# HF_front.net
KiCad netlist of a schematic drawn in EAGLE
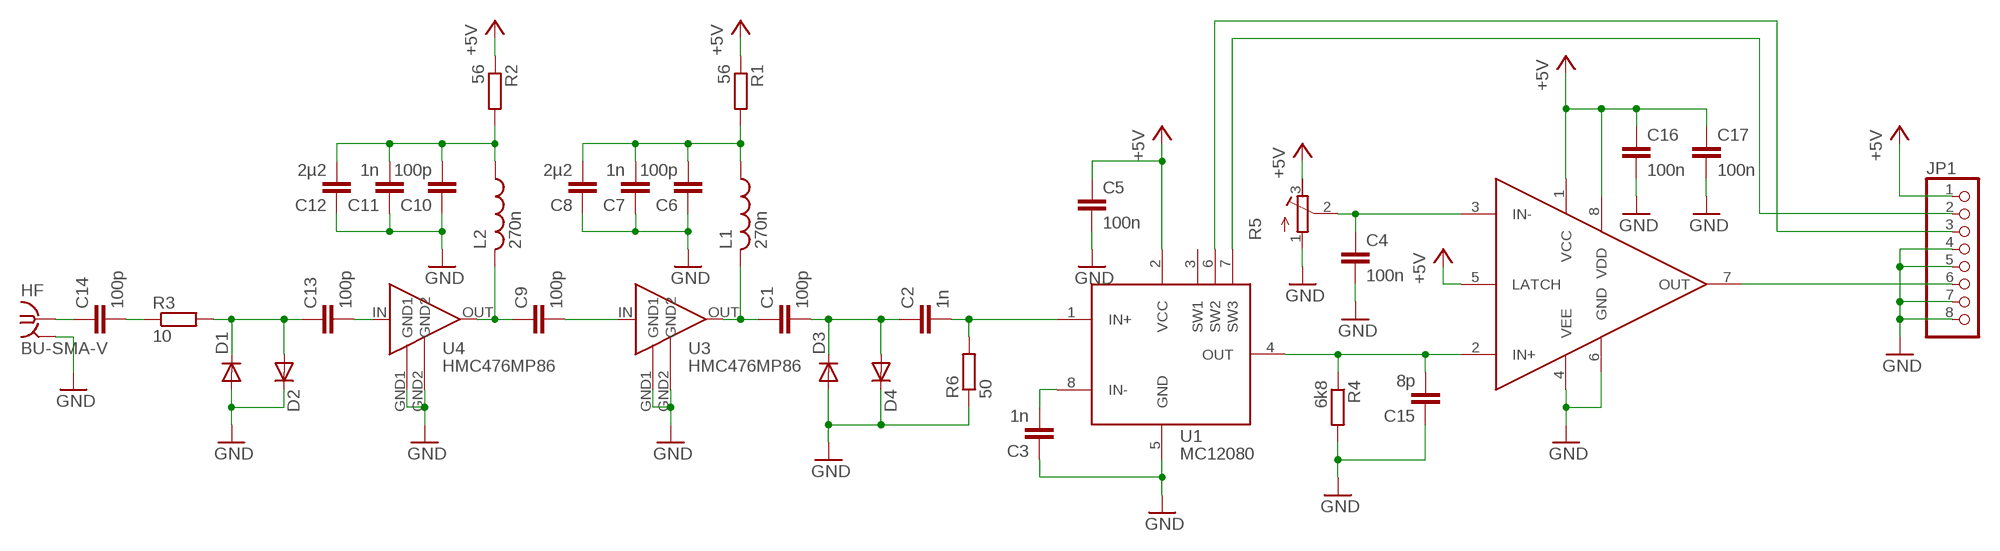
[diagram p0: schematic, sheet 1]

(export (version "E")
  (design (tool "Eeschema 10.0.6"))
  (components
    (comp (ref "C1")
      (value "100p")
      (footprint "eagle-import:C0603")
      (libsource (lib "eagle-import") (part "C-EUC0603"))
    )
    (comp (ref "C2")
      (value "1n")
      (footprint "eagle-import:C0603")
      (libsource (lib "eagle-import") (part "C-EUC0603"))
    )
    (comp (ref "C3")
      (value "1n")
      (footprint "eagle-import:C0603")
      (libsource (lib "eagle-import") (part "C-EUC0603"))
    )
    (comp (ref "C4")
      (value "100n")
      (footprint "eagle-import:C0603")
      (libsource (lib "eagle-import") (part "C-EUC0603"))
    )
    (comp (ref "C5")
      (value "100n")
      (footprint "eagle-import:C0603")
      (libsource (lib "eagle-import") (part "C-EUC0603"))
    )
    (comp (ref "C6")
      (value "100p")
      (footprint "eagle-import:C0603")
      (libsource (lib "eagle-import") (part "C-EUC0603"))
    )
    (comp (ref "C7")
      (value "1n")
      (footprint "eagle-import:C0603")
      (libsource (lib "eagle-import") (part "C-EUC0603"))
    )
    (comp (ref "C8")
      (value "2µ2")
      (footprint "eagle-import:C0603")
      (libsource (lib "eagle-import") (part "C-EUC0603"))
    )
    (comp (ref "C9")
      (value "100p")
      (footprint "eagle-import:C0603")
      (libsource (lib "eagle-import") (part "C-EUC0603"))
    )
    (comp (ref "C10")
      (value "100p")
      (footprint "eagle-import:C0603")
      (libsource (lib "eagle-import") (part "C-EUC0603"))
    )
    (comp (ref "C11")
      (value "1n")
      (footprint "eagle-import:C0603")
      (libsource (lib "eagle-import") (part "C-EUC0603"))
    )
    (comp (ref "C12")
      (value "2µ2")
      (footprint "eagle-import:C0603")
      (libsource (lib "eagle-import") (part "C-EUC0603"))
    )
    (comp (ref "C13")
      (value "100p")
      (footprint "eagle-import:C0603")
      (libsource (lib "eagle-import") (part "C-EUC0603"))
    )
    (comp (ref "C14")
      (value "100p")
      (footprint "eagle-import:C0603")
      (libsource (lib "eagle-import") (part "C-EUC0603"))
    )
    (comp (ref "C15")
      (value "8p")
      (footprint "eagle-import:C0603")
      (libsource (lib "eagle-import") (part "C-EUC0603"))
    )
    (comp (ref "C16")
      (value "100n")
      (footprint "eagle-import:C0603")
      (libsource (lib "eagle-import") (part "C-EUC0603"))
    )
    (comp (ref "C17")
      (value "100n")
      (footprint "eagle-import:C0603")
      (libsource (lib "eagle-import") (part "C-EUC0603"))
    )
    (comp (ref "D1")
      (value "DIODE-SOD323-W")
      (footprint "eagle-import:SOD323-W")
      (libsource (lib "eagle-import") (part "DIODE-SOD323-W"))
    )
    (comp (ref "D2")
      (value "DIODE-SOD323-W")
      (footprint "eagle-import:SOD323-W")
      (libsource (lib "eagle-import") (part "DIODE-SOD323-W"))
    )
    (comp (ref "D3")
      (value "DIODE-SOD323-W")
      (footprint "eagle-import:SOD323-W")
      (libsource (lib "eagle-import") (part "DIODE-SOD323-W"))
    )
    (comp (ref "D4")
      (value "DIODE-SOD323-W")
      (footprint "eagle-import:SOD323-W")
      (libsource (lib "eagle-import") (part "DIODE-SOD323-W"))
    )
    (comp (ref "HF")
      (value "BU-SMA-V")
      (footprint "eagle-import:BU-SMA-V")
      (libsource (lib "eagle-import") (part "BU-SMA-V"))
    )
    (comp (ref "JP1")
      (value "PINHD-1X8")
      (footprint "eagle-import:1X08")
      (libsource (lib "eagle-import") (part "PINHD-1X8"))
    )
    (comp (ref "L1")
      (value "270n")
      (footprint "eagle-import:R0603")
      (libsource (lib "eagle-import") (part "INDUCTOR0603"))
    )
    (comp (ref "L2")
      (value "270n")
      (footprint "eagle-import:R0603")
      (libsource (lib "eagle-import") (part "INDUCTOR0603"))
    )
    (comp (ref "R1")
      (value "56")
      (footprint "eagle-import:R0603")
      (libsource (lib "eagle-import") (part "R-EU_R0603"))
    )
    (comp (ref "R2")
      (value "56")
      (footprint "eagle-import:R0603")
      (libsource (lib "eagle-import") (part "R-EU_R0603"))
    )
    (comp (ref "R3")
      (value "10")
      (footprint "eagle-import:R0603")
      (libsource (lib "eagle-import") (part "R-EU_R0603"))
    )
    (comp (ref "R4")
      (value "6k8")
      (footprint "eagle-import:R0603")
      (libsource (lib "eagle-import") (part "R-EU_R0603"))
    )
    (comp (ref "R5")
      (value "R-TRIMM64W")
      (footprint "eagle-import:RTRIM64W")
      (libsource (lib "eagle-import") (part "R-TRIMM64W"))
    )
    (comp (ref "R6")
      (value "50")
      (footprint "eagle-import:R0603")
      (libsource (lib "eagle-import") (part "R-EU_R0603"))
    )
    (comp (ref "U1")
      (value "MC12080")
      (footprint "eagle-import:SOIC8")
      (libsource (lib "eagle-import") (part "MC12080"))
    )
    (comp (ref "U2")
      (value "MAX9203")
      (footprint "eagle-import:SOIC8")
      (libsource (lib "eagle-import") (part "MAX9203"))
    )
    (comp (ref "U3")
      (value "HMC476MP86")
      (footprint "eagle-import:MICRO-X")
      (libsource (lib "eagle-import") (part "HMC476MP86"))
    )
    (comp (ref "U4")
      (value "HMC476MP86")
      (footprint "eagle-import:MICRO-X")
      (libsource (lib "eagle-import") (part "HMC476MP86"))
    )
  )
  (nets
    (net (code "1") (name "+5V") (class "Default")
      (node (ref "C16") (pin "1") (pinfunction "1_1") (pintype "passive"))
      (node (ref "C17") (pin "1") (pinfunction "1_1") (pintype "passive"))
      (node (ref "C5") (pin "1") (pinfunction "1_1") (pintype "passive"))
      (node (ref "JP1") (pin "1") (pinfunction "1_1") (pintype "passive"))
      (node (ref "R1") (pin "1") (pinfunction "1_1") (pintype "passive"))
      (node (ref "R2") (pin "1") (pinfunction "1_1") (pintype "passive"))
      (node (ref "R5") (pin "3") (pinfunction "A_3") (pintype "passive"))
      (node (ref "U1") (pin "2") (pinfunction "VCC_2") (pintype "bidirectional"))
      (node (ref "U2") (pin "1") (pinfunction "VCC_1") (pintype "bidirectional"))
      (node (ref "U2") (pin "5") (pinfunction "LATCH_5") (pintype "bidirectional"))
      (node (ref "U2") (pin "8") (pinfunction "VDD_8") (pintype "bidirectional"))
    )
    (net (code "2") (name "GND") (class "Default")
      (node (ref "C10") (pin "1") (pinfunction "1_1") (pintype "passive"))
      (node (ref "C11") (pin "1") (pinfunction "1_1") (pintype "passive"))
      (node (ref "C12") (pin "1") (pinfunction "1_1") (pintype "passive"))
      (node (ref "C15") (pin "1") (pinfunction "1_1") (pintype "passive"))
      (node (ref "C16") (pin "2") (pinfunction "2_2") (pintype "passive"))
      (node (ref "C17") (pin "2") (pinfunction "2_2") (pintype "passive"))
      (node (ref "C3") (pin "1") (pinfunction "1_1") (pintype "passive"))
      (node (ref "C4") (pin "2") (pinfunction "2_2") (pintype "passive"))
      (node (ref "C5") (pin "2") (pinfunction "2_2") (pintype "passive"))
      (node (ref "C6") (pin "1") (pinfunction "1_1") (pintype "passive"))
      (node (ref "C7") (pin "1") (pinfunction "1_1") (pintype "passive"))
      (node (ref "C8") (pin "1") (pinfunction "1_1") (pintype "passive"))
      (node (ref "D1") (pin "A") (pinfunction "A_A") (pintype "passive"))
      (node (ref "D2") (pin "C") (pinfunction "C_C") (pintype "passive"))
      (node (ref "D3") (pin "A") (pinfunction "A_A") (pintype "passive"))
      (node (ref "D4") (pin "C") (pinfunction "C_C") (pintype "passive"))
      (node (ref "HF") (pin "2") (pinfunction "2_2") (pintype "passive"))
      (node (ref "HF") (pin "3") (pinfunction "2_3") (pintype "passive"))
      (node (ref "HF") (pin "4") (pinfunction "2_4") (pintype "passive"))
      (node (ref "HF") (pin "5") (pinfunction "2_5") (pintype "passive"))
      (node (ref "JP1") (pin "4") (pinfunction "4_4") (pintype "passive"))
      (node (ref "JP1") (pin "5") (pinfunction "5_5") (pintype "passive"))
      (node (ref "JP1") (pin "7") (pinfunction "7_7") (pintype "passive"))
      (node (ref "JP1") (pin "8") (pinfunction "8_8") (pintype "passive"))
      (node (ref "R4") (pin "2") (pinfunction "2_2") (pintype "passive"))
      (node (ref "R5") (pin "1") (pinfunction "E_1") (pintype "passive"))
      (node (ref "R6") (pin "1") (pinfunction "1_1") (pintype "passive"))
      (node (ref "U1") (pin "5") (pinfunction "GND_5") (pintype "bidirectional"))
      (node (ref "U2") (pin "4") (pinfunction "VEE_4") (pintype "bidirectional"))
      (node (ref "U2") (pin "6") (pinfunction "GND_6") (pintype "bidirectional"))
      (node (ref "U3") (pin "GND1") (pinfunction "GND1_GND1") (pintype "power_in"))
      (node (ref "U3") (pin "GND2") (pinfunction "GND2_GND2") (pintype "power_in"))
      (node (ref "U4") (pin "GND1") (pinfunction "GND1_GND1") (pintype "power_in"))
      (node (ref "U4") (pin "GND2") (pinfunction "GND2_GND2") (pintype "power_in"))
    )
    (net (code "3") (name "Net-(C1-Pad1)") (class "Default")
      (node (ref "C1") (pin "1") (pinfunction "1_1") (pintype "passive"))
      (node (ref "L1") (pin "2") (pinfunction "2_2") (pintype "passive"))
      (node (ref "U3") (pin "OUT") (pinfunction "OUT_OUT") (pintype "output"))
    )
    (net (code "4") (name "Net-(C1-Pad2)") (class "Default")
      (node (ref "C1") (pin "2") (pinfunction "2_2") (pintype "passive"))
      (node (ref "C2") (pin "1") (pinfunction "1_1") (pintype "passive"))
      (node (ref "D3") (pin "C") (pinfunction "C_C") (pintype "passive"))
      (node (ref "D4") (pin "A") (pinfunction "A_A") (pintype "passive"))
    )
    (net (code "5") (name "Net-(C6-Pad2)") (class "Default")
      (node (ref "C6") (pin "2") (pinfunction "2_2") (pintype "passive"))
      (node (ref "C7") (pin "2") (pinfunction "2_2") (pintype "passive"))
      (node (ref "C8") (pin "2") (pinfunction "2_2") (pintype "passive"))
      (node (ref "L1") (pin "1") (pinfunction "1_1") (pintype "passive"))
      (node (ref "R1") (pin "2") (pinfunction "2_2") (pintype "passive"))
    )
    (net (code "6") (name "Net-(C9-Pad1)") (class "Default")
      (node (ref "C9") (pin "1") (pinfunction "1_1") (pintype "passive"))
      (node (ref "L2") (pin "2") (pinfunction "2_2") (pintype "passive"))
      (node (ref "U4") (pin "OUT") (pinfunction "OUT_OUT") (pintype "output"))
    )
    (net (code "7") (name "Net-(C9-Pad2)") (class "Default")
      (node (ref "C9") (pin "2") (pinfunction "2_2") (pintype "passive"))
      (node (ref "U3") (pin "IN") (pinfunction "IN_IN") (pintype "input"))
    )
    (net (code "8") (name "Net-(C10-Pad2)") (class "Default")
      (node (ref "C10") (pin "2") (pinfunction "2_2") (pintype "passive"))
      (node (ref "C11") (pin "2") (pinfunction "2_2") (pintype "passive"))
      (node (ref "C12") (pin "2") (pinfunction "2_2") (pintype "passive"))
      (node (ref "L2") (pin "1") (pinfunction "1_1") (pintype "passive"))
      (node (ref "R2") (pin "2") (pinfunction "2_2") (pintype "passive"))
    )
    (net (code "9") (name "Net-(C13-Pad1)") (class "Default")
      (node (ref "C13") (pin "1") (pinfunction "1_1") (pintype "passive"))
      (node (ref "D1") (pin "C") (pinfunction "C_C") (pintype "passive"))
      (node (ref "D2") (pin "A") (pinfunction "A_A") (pintype "passive"))
      (node (ref "R3") (pin "2") (pinfunction "2_2") (pintype "passive"))
    )
    (net (code "10") (name "Net-(C13-Pad2)") (class "Default")
      (node (ref "C13") (pin "2") (pinfunction "2_2") (pintype "passive"))
      (node (ref "U4") (pin "IN") (pinfunction "IN_IN") (pintype "input"))
    )
    (net (code "11") (name "Net-(C14-Pad1)") (class "Default")
      (node (ref "C14") (pin "1") (pinfunction "1_1") (pintype "passive"))
      (node (ref "HF") (pin "1") (pinfunction "1_1") (pintype "passive"))
    )
    (net (code "12") (name "Net-(C14-Pad2)") (class "Default")
      (node (ref "C14") (pin "2") (pinfunction "2_2") (pintype "passive"))
      (node (ref "R3") (pin "1") (pinfunction "1_1") (pintype "passive"))
    )
    (net (code "13") (name "Net-(R5-S)") (class "Default")
      (node (ref "C4") (pin "1") (pinfunction "1_1") (pintype "passive"))
      (node (ref "R5") (pin "2") (pinfunction "S_2") (pintype "passive"))
      (node (ref "U2") (pin "3") (pinfunction "IN-_3") (pintype "bidirectional"))
    )
    (net (code "14") (name "Net-(U1-IN+)") (class "Default")
      (node (ref "C2") (pin "2") (pinfunction "2_2") (pintype "passive"))
      (node (ref "R6") (pin "2") (pinfunction "2_2") (pintype "passive"))
      (node (ref "U1") (pin "1") (pinfunction "IN+_1") (pintype "bidirectional"))
    )
    (net (code "15") (name "Net-(U1-IN-)") (class "Default")
      (node (ref "C3") (pin "2") (pinfunction "2_2") (pintype "passive"))
      (node (ref "U1") (pin "8") (pinfunction "IN-_8") (pintype "bidirectional"))
    )
    (net (code "16") (name "Net-(U1-OUT)") (class "Default")
      (node (ref "C15") (pin "2") (pinfunction "2_2") (pintype "passive"))
      (node (ref "R4") (pin "1") (pinfunction "1_1") (pintype "passive"))
      (node (ref "U1") (pin "4") (pinfunction "OUT_4") (pintype "bidirectional"))
      (node (ref "U2") (pin "2") (pinfunction "IN+_2") (pintype "bidirectional"))
    )
    (net (code "17") (name "Net-(U1-SW2)") (class "Default")
      (node (ref "JP1") (pin "3") (pinfunction "3_3") (pintype "passive"))
      (node (ref "U1") (pin "6") (pinfunction "SW2_6") (pintype "bidirectional"))
    )
    (net (code "18") (name "Net-(U1-SW3)") (class "Default")
      (node (ref "JP1") (pin "2") (pinfunction "2_2") (pintype "passive"))
      (node (ref "U1") (pin "7") (pinfunction "SW3_7") (pintype "bidirectional"))
    )
    (net (code "19") (name "Net-(U2-OUT)") (class "Default")
      (node (ref "JP1") (pin "6") (pinfunction "6_6") (pintype "passive"))
      (node (ref "U2") (pin "7") (pinfunction "OUT_7") (pintype "bidirectional"))
    )
    (net (code "20") (name "unconnected-(U1-SW1-Pad3)") (class "Default")
      (node (ref "U1") (pin "3") (pinfunction "SW1_3") (pintype "bidirectional"))
    )
  )
)
